# Main.net
KiCad netlist of a schematic drawn in Altium Designer
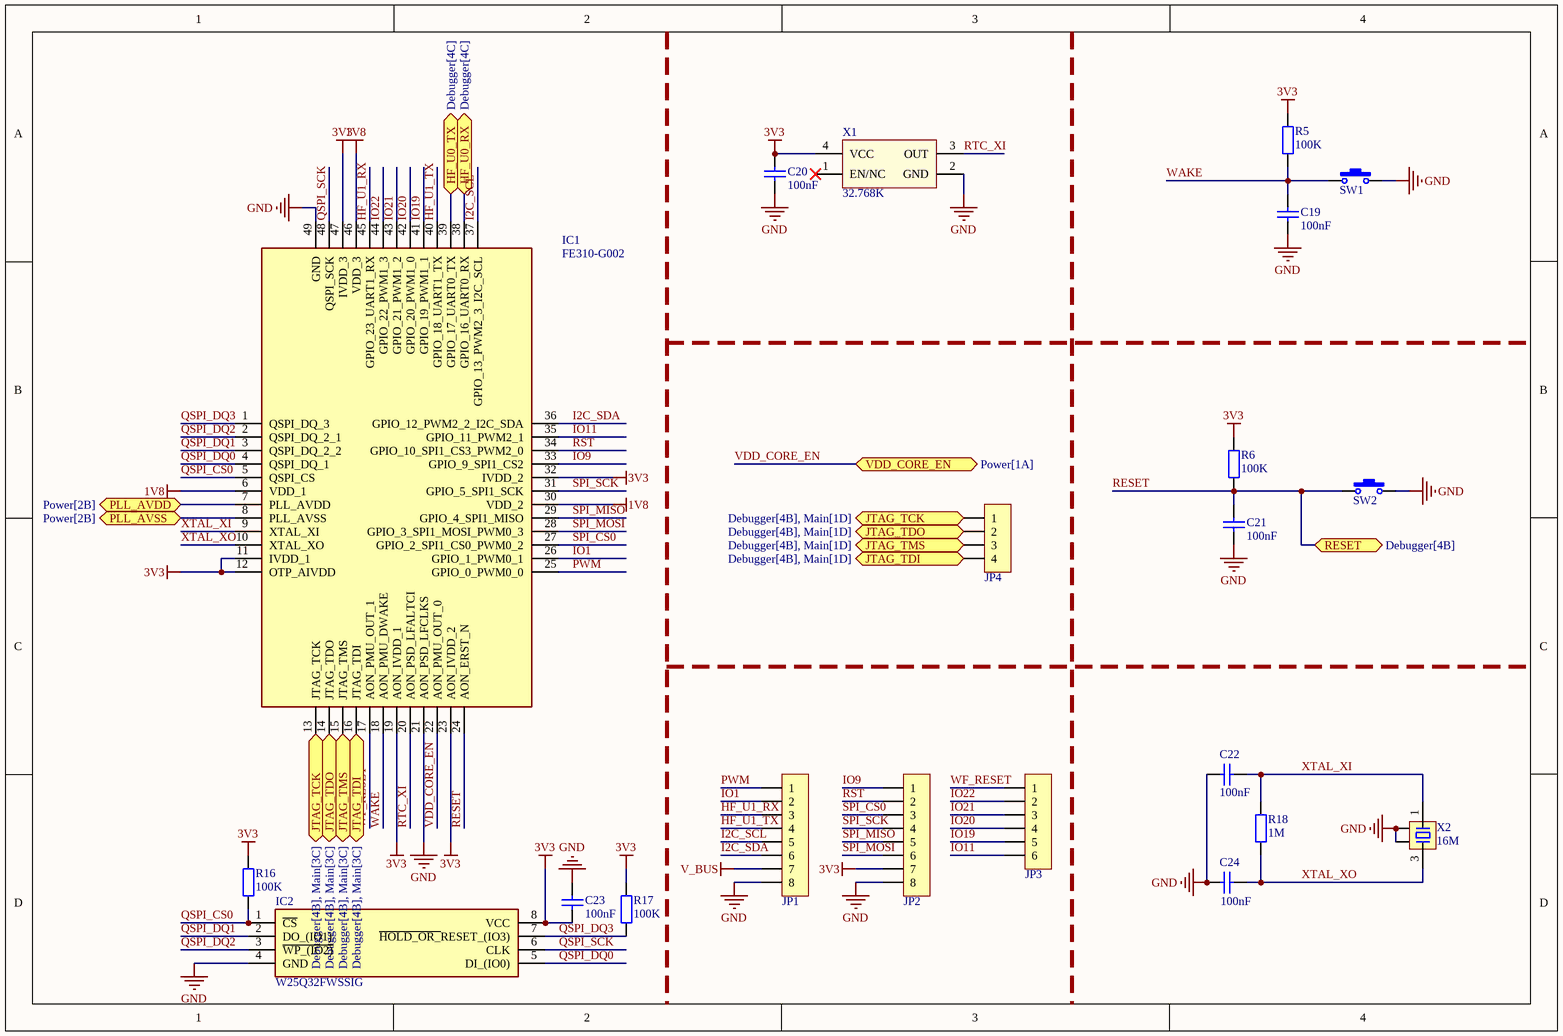
[diagram p0: Main.SchDoc]

(export (version "E")
  (design (tool "Eeschema 10.0.6"))
  (components
    (comp (ref "C19")
      (value "100nF")
      (footprint "C0603_NS")
      (description "贴片电容/MLCC电容")
      (libsource (lib "0.1 - 电阻-电容-电感-晶振-晶体-磁珠-电位器-法拉电容-馈通电容") (part "C"))
    )
    (comp (ref "C20")
      (value "100nF")
      (footprint "C0603_NS")
      (description "贴片电容/MLCC电容")
      (libsource (lib "0.1 - 电阻-电容-电感-晶振-晶体-磁珠-电位器-法拉电容-馈通电容") (part "C"))
    )
    (comp (ref "C21")
      (value "100nF")
      (footprint "C0603_NS")
      (description "贴片电容/MLCC电容")
      (libsource (lib "0.1 - 电阻-电容-电感-晶振-晶体-磁珠-电位器-法拉电容-馈通电容") (part "C"))
    )
    (comp (ref "C22")
      (value "100nF")
      (footprint "C0603_NS")
      (description "贴片电容/MLCC电容")
      (libsource (lib "0.1 - 电阻-电容-电感-晶振-晶体-磁珠-电位器-法拉电容-馈通电容") (part "C"))
    )
    (comp (ref "C23")
      (value "100nF")
      (footprint "C0603_NS")
      (description "贴片电容/MLCC电容")
      (libsource (lib "0.1 - 电阻-电容-电感-晶振-晶体-磁珠-电位器-法拉电容-馈通电容") (part "C"))
    )
    (comp (ref "C24")
      (value "100nF")
      (footprint "C0603_NS")
      (description "贴片电容/MLCC电容")
      (libsource (lib "0.1 - 电阻-电容-电感-晶振-晶体-磁珠-电位器-法拉电容-馈通电容") (part "C"))
    )
    (comp (ref "IC1")
      (value "FE310-G002")
      (footprint "SamacSys:QFN40P600X600X93-49N")
      (description "Integrated Circuit")
      (libsource (lib "*") (part "FE310-G002"))
    )
    (comp (ref "IC2")
      (value "W25Q32FWSSIG")
      (footprint "SamacSys:SOIC127P790X216-8N")
      (description "Integrated Circuit")
      (fields (field (name "MOUSER PART NUMBER") "454-W25Q32FWSSIG"))
      (libsource (lib "*") (part "W25Q32FWSSIG"))
    )
    (comp (ref "JP1")
      (value "HDR-1X8")
      (footprint "HDR2.54-M-LI-8P")
      (description "8P接插件")
      (libsource (lib "5.5 - 2.54mm连接器(KF2EDGK_XH2.54_2.54排针排母)") (part "Header 8"))
    )
    (comp (ref "JP2")
      (value "HDR-1X8")
      (footprint "HDR2.54-M-LI-8P")
      (description "8P接插件")
      (libsource (lib "5.5 - 2.54mm连接器(KF2EDGK_XH2.54_2.54排针排母)") (part "Header 8"))
    )
    (comp (ref "JP3")
      (value "HDR-1X6")
      (footprint "HDR2.54-LI-6P")
      (description "6P接插件")
      (libsource (lib "5.5 - 2.54mm连接器(KF2EDGK_XH2.54_2.54排针排母)") (part "Header 6"))
    )
    (comp (ref "JP4")
      (value "HDR-1X4")
      (footprint "HDR2.54-LI-4P")
      (description "4P接插件")
      (libsource (lib "5.5 - 2.54mm连接器(KF2EDGK_XH2.54_2.54排针排母)") (part "Header 4"))
    )
    (comp (ref "R5")
      (value "100K")
      (footprint "R0603_NS")
      (description "贴片电阻")
      (libsource (lib "0.1 - 电阻-电容-电感-晶振-晶体-磁珠-电位器-法拉电容-馈通电容") (part "R"))
    )
    (comp (ref "R6")
      (value "100K")
      (footprint "R0603_NS")
      (description "贴片电阻")
      (libsource (lib "0.1 - 电阻-电容-电感-晶振-晶体-磁珠-电位器-法拉电容-馈通电容") (part "R"))
    )
    (comp (ref "R16")
      (value "100K")
      (footprint "R0603_NS")
      (description "贴片电阻")
      (libsource (lib "0.1 - 电阻-电容-电感-晶振-晶体-磁珠-电位器-法拉电容-馈通电容") (part "R"))
    )
    (comp (ref "R17")
      (value "100K")
      (footprint "R0603_NS")
      (description "贴片电阻")
      (libsource (lib "0.1 - 电阻-电容-电感-晶振-晶体-磁珠-电位器-法拉电容-馈通电容") (part "R"))
    )
    (comp (ref "R18")
      (value "1M")
      (footprint "R0603_NS")
      (description "贴片电阻")
      (libsource (lib "0.1 - 电阻-电容-电感-晶振-晶体-磁珠-电位器-法拉电容-馈通电容") (part "R"))
    )
    (comp (ref "SW1")
      (value "3x6x5")
      (footprint "SW SMD-3*6*2.5")
      (description "3x6轻触开关")
      (libsource (lib "0.5 - 按键_开关_蜂鸣器_保险丝_电池_测试点_Mark点_铜柱") (part "SW 3x6"))
    )
    (comp (ref "SW2")
      (value "3x6x5")
      (footprint "SW SMD-3*6*2.5")
      (description "3x6轻触开关")
      (libsource (lib "0.5 - 按键_开关_蜂鸣器_保险丝_电池_测试点_Mark点_铜柱") (part "SW 3x6"))
    )
    (comp (ref "X1")
      (value "32.768K")
      (footprint "OSC-3225-4P")
      (description "4脚有源晶振(振荡器)")
      (libsource (lib "0.1 - 电阻-电容-电感-晶振-晶体-磁珠-电位器-法拉电容-馈通电容") (part "XTAL-ACT-4P"))
    )
    (comp (ref "X2")
      (value "16M")
      (footprint "XTAL-3225-4P")
      (description "4脚无源晶振(谐振器）")
      (libsource (lib "0.1 - 电阻-电容-电感-晶振-晶体-磁珠-电位器-法拉电容-馈通电容") (part "XTAL-4P"))
    )
  )
  (nets
    (net (code "1") (name "/HF_U0_RX") (class "Default")
      (node (ref "IC1") (pin "38") (pinfunction "GPIO_16_UART0_RX_38") (pintype "passive"))
    )
    (net (code "2") (name "/HF_U0_TX") (class "Default")
      (node (ref "IC1") (pin "39") (pinfunction "GPIO_17_UART0_TX_39") (pintype "passive"))
    )
    (net (code "3") (name "/HF_U1_RX") (class "Default")
      (node (ref "IC1") (pin "45") (pinfunction "GPIO_23_UART1_RX_45") (pintype "passive"))
      (node (ref "JP1") (pin "3") (pinfunction "3_3") (pintype "passive"))
    )
    (net (code "4") (name "/HF_U1_TX") (class "Default")
      (node (ref "IC1") (pin "40") (pinfunction "GPIO_18_UART1_TX_40") (pintype "passive"))
      (node (ref "JP1") (pin "4") (pinfunction "4_4") (pintype "passive"))
    )
    (net (code "5") (name "/I2C_SCL") (class "Default")
      (node (ref "IC1") (pin "37") (pinfunction "GPIO_13_PWM2_3_I2C_SCL_37") (pintype "passive"))
      (node (ref "JP1") (pin "5") (pinfunction "5_5") (pintype "passive"))
    )
    (net (code "6") (name "/I2C_SDA") (class "Default")
      (node (ref "IC1") (pin "36") (pinfunction "GPIO_12_PWM2_2_I2C_SDA_36") (pintype "passive"))
      (node (ref "JP1") (pin "6") (pinfunction "6_6") (pintype "passive"))
    )
    (net (code "7") (name "/IO1") (class "Default")
      (node (ref "IC1") (pin "26") (pinfunction "GPIO_1_PWM0_1_26") (pintype "passive"))
      (node (ref "JP1") (pin "2") (pinfunction "2_2") (pintype "passive"))
    )
    (net (code "8") (name "/IO9") (class "Default")
      (node (ref "IC1") (pin "33") (pinfunction "GPIO_9_SPI1_CS2_33") (pintype "passive"))
      (node (ref "JP2") (pin "1") (pinfunction "1_1") (pintype "passive"))
    )
    (net (code "9") (name "/IO11") (class "Default")
      (node (ref "IC1") (pin "35") (pinfunction "GPIO_11_PWM2_1_35") (pintype "passive"))
      (node (ref "JP3") (pin "6") (pinfunction "6_6") (pintype "passive"))
    )
    (net (code "10") (name "/IO19") (class "Default")
      (node (ref "IC1") (pin "41") (pinfunction "GPIO_19_PWM1_1_41") (pintype "passive"))
      (node (ref "JP3") (pin "5") (pinfunction "5_5") (pintype "passive"))
    )
    (net (code "11") (name "/IO20") (class "Default")
      (node (ref "IC1") (pin "42") (pinfunction "GPIO_20_PWM1_0_42") (pintype "passive"))
      (node (ref "JP3") (pin "4") (pinfunction "4_4") (pintype "passive"))
    )
    (net (code "12") (name "/IO21") (class "Default")
      (node (ref "IC1") (pin "43") (pinfunction "GPIO_21_PWM1_2_43") (pintype "passive"))
      (node (ref "JP3") (pin "3") (pinfunction "3_3") (pintype "passive"))
    )
    (net (code "13") (name "/IO22") (class "Default")
      (node (ref "IC1") (pin "44") (pinfunction "GPIO_22_PWM1_3_44") (pintype "passive"))
      (node (ref "JP3") (pin "2") (pinfunction "2_2") (pintype "passive"))
    )
    (net (code "14") (name "/JTAG_TCK") (class "Default")
      (node (ref "IC1") (pin "13") (pinfunction "JTAG_TCK_13") (pintype "passive"))
      (node (ref "JP4") (pin "1") (pinfunction "1_1") (pintype "passive"))
    )
    (net (code "15") (name "/JTAG_TDI") (class "Default")
      (node (ref "IC1") (pin "16") (pinfunction "JTAG_TDI_16") (pintype "passive"))
      (node (ref "JP4") (pin "4") (pinfunction "4_4") (pintype "passive"))
    )
    (net (code "16") (name "/JTAG_TDO") (class "Default")
      (node (ref "IC1") (pin "14") (pinfunction "JTAG_TDO_14") (pintype "passive"))
      (node (ref "JP4") (pin "2") (pinfunction "2_2") (pintype "passive"))
    )
    (net (code "17") (name "/JTAG_TMS") (class "Default")
      (node (ref "IC1") (pin "15") (pinfunction "JTAG_TMS_15") (pintype "passive"))
      (node (ref "JP4") (pin "3") (pinfunction "3_3") (pintype "passive"))
    )
    (net (code "18") (name "/PLL_AVDD") (class "Default")
      (node (ref "IC1") (pin "7") (pinfunction "PLL_AVDD_7") (pintype "passive"))
    )
    (net (code "19") (name "/PLL_AVSS") (class "Default")
      (node (ref "IC1") (pin "8") (pinfunction "PLL_AVSS_8") (pintype "passive"))
    )
    (net (code "20") (name "/PWM") (class "Default")
      (node (ref "IC1") (pin "25") (pinfunction "GPIO_0_PWM0_0_25") (pintype "passive"))
      (node (ref "JP1") (pin "1") (pinfunction "1_1") (pintype "passive"))
    )
    (net (code "21") (name "/QSPI_CS0") (class "Default")
      (node (ref "IC1") (pin "5") (pinfunction "QSPI_CS_5") (pintype "passive"))
      (node (ref "IC2") (pin "1") (pinfunction "~{CS}_1") (pintype "passive"))
      (node (ref "R16") (pin "1") (pinfunction "1_1") (pintype "passive"))
    )
    (net (code "22") (name "/QSPI_DQ0") (class "Default")
      (node (ref "IC1") (pin "4") (pinfunction "QSPI_DQ_1_4") (pintype "passive"))
      (node (ref "IC2") (pin "5") (pinfunction "DI_(IO0)_5") (pintype "passive"))
    )
    (net (code "23") (name "/QSPI_DQ1") (class "Default")
      (node (ref "IC1") (pin "3") (pinfunction "QSPI_DQ_2_2_3") (pintype "passive"))
      (node (ref "IC2") (pin "2") (pinfunction "DO_(IO1)_2") (pintype "passive"))
    )
    (net (code "24") (name "/QSPI_DQ2") (class "Default")
      (node (ref "IC1") (pin "2") (pinfunction "QSPI_DQ_2_1_2") (pintype "passive"))
      (node (ref "IC2") (pin "3") (pinfunction "~{WP_(IO2)}_3") (pintype "passive"))
    )
    (net (code "25") (name "/QSPI_DQ3") (class "Default")
      (node (ref "IC1") (pin "1") (pinfunction "QSPI_DQ_3_1") (pintype "passive"))
      (node (ref "IC2") (pin "7") (pinfunction "~{HOLD_OR_}RESET_(IO3)_7") (pintype "passive"))
      (node (ref "R17") (pin "1") (pinfunction "1_1") (pintype "passive"))
    )
    (net (code "26") (name "/QSPI_SCK") (class "Default")
      (node (ref "IC1") (pin "48") (pinfunction "QSPI_SCK_48") (pintype "passive"))
      (node (ref "IC2") (pin "6") (pinfunction "CLK_6") (pintype "passive"))
    )
    (net (code "27") (name "/RESET") (class "Default")
      (node (ref "C21") (pin "2") (pinfunction "2_2") (pintype "passive"))
      (node (ref "IC1") (pin "24") (pinfunction "AON_ERST_N_24") (pintype "passive"))
      (node (ref "R6") (pin "1") (pinfunction "1_1") (pintype "passive"))
      (node (ref "SW2") (pin "1") (pinfunction "1_1") (pintype "passive"))
    )
    (net (code "28") (name "/RST") (class "Default")
      (node (ref "IC1") (pin "34") (pinfunction "GPIO_10_SPI1_CS3_PWM2_0_34") (pintype "passive"))
      (node (ref "JP2") (pin "2") (pinfunction "2_2") (pintype "passive"))
    )
    (net (code "29") (name "/RTC_XI") (class "Default")
      (node (ref "IC1") (pin "20") (pinfunction "AON_PSD_LFALTCI_20") (pintype "passive"))
      (node (ref "X1") (pin "3") (pinfunction "OUT_3") (pintype "passive"))
    )
    (net (code "30") (name "/SPI_CS0") (class "Default")
      (node (ref "IC1") (pin "27") (pinfunction "GPIO_2_SPI1_CS0_PWM0_2_27") (pintype "passive"))
      (node (ref "JP2") (pin "3") (pinfunction "3_3") (pintype "passive"))
    )
    (net (code "31") (name "/SPI_MISO") (class "Default")
      (node (ref "IC1") (pin "29") (pinfunction "GPIO_4_SPI1_MISO_29") (pintype "passive"))
      (node (ref "JP2") (pin "5") (pinfunction "5_5") (pintype "passive"))
    )
    (net (code "32") (name "/SPI_MOSI") (class "Default")
      (node (ref "IC1") (pin "28") (pinfunction "GPIO_3_SPI1_MOSI_PWM0_3_28") (pintype "passive"))
      (node (ref "JP2") (pin "6") (pinfunction "6_6") (pintype "passive"))
    )
    (net (code "33") (name "/SPI_SCK") (class "Default")
      (node (ref "IC1") (pin "31") (pinfunction "GPIO_5_SPI1_SCK_31") (pintype "passive"))
      (node (ref "JP2") (pin "4") (pinfunction "4_4") (pintype "passive"))
    )
    (net (code "34") (name "/VDD_CORE_EN") (class "Default")
      (node (ref "IC1") (pin "22") (pinfunction "AON_PMU_OUT_0_22") (pintype "passive"))
    )
    (net (code "35") (name "/WAKE") (class "Default")
      (node (ref "C19") (pin "2") (pinfunction "2_2") (pintype "passive"))
      (node (ref "IC1") (pin "18") (pinfunction "AON_PMU_DWAKE_18") (pintype "passive"))
      (node (ref "R5") (pin "1") (pinfunction "1_1") (pintype "passive"))
      (node (ref "SW1") (pin "1") (pinfunction "1_1") (pintype "passive"))
    )
    (net (code "36") (name "/WF_RESET") (class "Default")
      (node (ref "IC1") (pin "17") (pinfunction "AON_PMU_OUT_1_17") (pintype "passive"))
      (node (ref "JP3") (pin "1") (pinfunction "1_1") (pintype "passive"))
    )
    (net (code "37") (name "/XTAL_XI") (class "Default")
      (node (ref "C22") (pin "2") (pinfunction "2_2") (pintype "passive"))
      (node (ref "IC1") (pin "9") (pinfunction "XTAL_XI_9") (pintype "passive"))
      (node (ref "R18") (pin "2") (pinfunction "2_2") (pintype "passive"))
      (node (ref "X2") (pin "1") (pinfunction "1_1") (pintype "passive"))
    )
    (net (code "38") (name "/XTAL_XO") (class "Default")
      (node (ref "C24") (pin "1") (pinfunction "1_1") (pintype "passive"))
      (node (ref "IC1") (pin "10") (pinfunction "XTAL_XO_10") (pintype "passive"))
      (node (ref "R18") (pin "1") (pinfunction "1_1") (pintype "passive"))
      (node (ref "X2") (pin "3") (pinfunction "3_3") (pintype "passive"))
    )
    (net (code "39") (name "1V8") (class "Default")
      (node (ref "IC1") (pin "30") (pinfunction "VDD_2_30") (pintype "passive"))
      (node (ref "IC1") (pin "46") (pinfunction "VDD_3_46") (pintype "passive"))
      (node (ref "IC1") (pin "6") (pinfunction "VDD_1_6") (pintype "passive"))
    )
    (net (code "40") (name "3V3") (class "Default")
      (node (ref "C20") (pin "2") (pinfunction "2_2") (pintype "passive"))
      (node (ref "C23") (pin "1") (pinfunction "1_1") (pintype "passive"))
      (node (ref "IC1") (pin "11") (pinfunction "IVDD_1_11") (pintype "passive"))
      (node (ref "IC1") (pin "12") (pinfunction "OTP_AIVDD_12") (pintype "passive"))
      (node (ref "IC1") (pin "19") (pinfunction "AON_IVDD_1_19") (pintype "passive"))
      (node (ref "IC1") (pin "23") (pinfunction "AON_IVDD_2_23") (pintype "passive"))
      (node (ref "IC1") (pin "32") (pinfunction "IVDD_2_32") (pintype "passive"))
      (node (ref "IC1") (pin "47") (pinfunction "IVDD_3_47") (pintype "passive"))
      (node (ref "IC2") (pin "8") (pinfunction "VCC_8") (pintype "passive"))
      (node (ref "JP2") (pin "7") (pinfunction "7_7") (pintype "passive"))
      (node (ref "R16") (pin "2") (pinfunction "2_2") (pintype "passive"))
      (node (ref "R17") (pin "2") (pinfunction "2_2") (pintype "passive"))
      (node (ref "R5") (pin "2") (pinfunction "2_2") (pintype "passive"))
      (node (ref "R6") (pin "2") (pinfunction "2_2") (pintype "passive"))
      (node (ref "X1") (pin "4") (pinfunction "VCC_4") (pintype "passive"))
    )
    (net (code "41") (name "GND") (class "Default")
      (node (ref "C19") (pin "1") (pinfunction "1_1") (pintype "passive"))
      (node (ref "C20") (pin "1") (pinfunction "1_1") (pintype "passive"))
      (node (ref "C21") (pin "1") (pinfunction "1_1") (pintype "passive"))
      (node (ref "C22") (pin "1") (pinfunction "1_1") (pintype "passive"))
      (node (ref "C23") (pin "2") (pinfunction "2_2") (pintype "passive"))
      (node (ref "C24") (pin "2") (pinfunction "2_2") (pintype "passive"))
      (node (ref "IC1") (pin "21") (pinfunction "AON_PSD_LFCLKS_21") (pintype "passive"))
      (node (ref "IC1") (pin "49") (pinfunction "GND_49") (pintype "passive"))
      (node (ref "IC2") (pin "4") (pinfunction "GND_4") (pintype "passive"))
      (node (ref "JP1") (pin "8") (pinfunction "8_8") (pintype "passive"))
      (node (ref "JP2") (pin "8") (pinfunction "8_8") (pintype "passive"))
      (node (ref "SW1") (pin "2") (pinfunction "2_2") (pintype "passive"))
      (node (ref "SW2") (pin "2") (pinfunction "2_2") (pintype "passive"))
      (node (ref "X1") (pin "2") (pinfunction "GND_2") (pintype "passive"))
      (node (ref "X2") (pin "2") (pinfunction "2_2") (pintype "passive"))
      (node (ref "X2") (pin "4") (pinfunction "4_4") (pintype "passive"))
    )
    (net (code "42") (name "V_BUS") (class "Default")
      (node (ref "JP1") (pin "7") (pinfunction "7_7") (pintype "passive"))
    )
    (net (code "43") (name "unconnected-(X1-EN{slash}NC-Pad1)") (class "Default")
      (node (ref "X1") (pin "1") (pinfunction "EN/NC_1") (pintype "passive+no_connect"))
    )
  )
)
